# trif_M.net
KiCad netlist of a schematic drawn in EAGLE
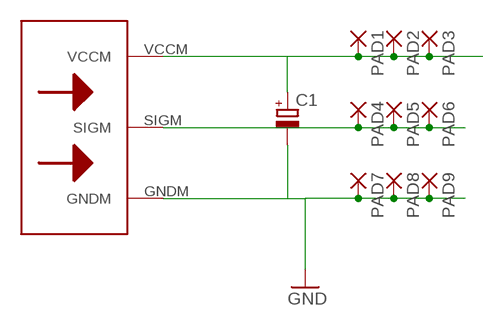
[diagram p0: schematic, sheet 1]

(export (version "E")
  (design (tool "Eeschema 10.0.6"))
  (components
    (comp (ref "C1")
      (value "CPOL-EU153CLV-1012")
      (footprint "eagle-import:153CLV-1012")
      (libsource (lib "eagle-import") (part "CPOL-EU153CLV-1012"))
    )
    (comp (ref "PAD1")
      (value "SMD2")
      (footprint "eagle-import:SMD1,27-2,54")
      (libsource (lib "eagle-import") (part "SMD2"))
    )
    (comp (ref "PAD2")
      (value "SMD2")
      (footprint "eagle-import:SMD1,27-2,54")
      (libsource (lib "eagle-import") (part "SMD2"))
    )
    (comp (ref "PAD3")
      (value "SMD2")
      (footprint "eagle-import:SMD1,27-2,54")
      (libsource (lib "eagle-import") (part "SMD2"))
    )
    (comp (ref "PAD4")
      (value "SMD2")
      (footprint "eagle-import:SMD1,27-2,54")
      (libsource (lib "eagle-import") (part "SMD2"))
    )
    (comp (ref "PAD5")
      (value "SMD2")
      (footprint "eagle-import:SMD1,27-2,54")
      (libsource (lib "eagle-import") (part "SMD2"))
    )
    (comp (ref "PAD6")
      (value "SMD2")
      (footprint "eagle-import:SMD1,27-2,54")
      (libsource (lib "eagle-import") (part "SMD2"))
    )
    (comp (ref "PAD7")
      (value "SMD2")
      (footprint "eagle-import:SMD1,27-2,54")
      (libsource (lib "eagle-import") (part "SMD2"))
    )
    (comp (ref "PAD8")
      (value "SMD2")
      (footprint "eagle-import:SMD1,27-2,54")
      (libsource (lib "eagle-import") (part "SMD2"))
    )
    (comp (ref "PAD9")
      (value "SMD2")
      (footprint "eagle-import:SMD1,27-2,54")
      (libsource (lib "eagle-import") (part "SMD2"))
    )
    (comp (ref "U$1")
      (value "BITWIREM")
      (footprint "eagle-import:BITWIREM")
      (libsource (lib "eagle-import") (part "BITWIREM"))
    )
  )
  (nets
    (net (code "1") (name "GND") (class "Default")
      (node (ref "C1") (pin "-") (pinfunction "-_-") (pintype "passive"))
      (node (ref "PAD7") (pin "1") (pinfunction "P_1") (pintype "passive"))
      (node (ref "PAD8") (pin "1") (pinfunction "P_1") (pintype "passive"))
      (node (ref "PAD9") (pin "1") (pinfunction "P_1") (pintype "passive"))
      (node (ref "U$1") (pin "GNDM") (pinfunction "GNDM_GNDM") (pintype "bidirectional"))
    )
    (net (code "2") (name "Net-(PAD1-P)") (class "Default")
      (node (ref "C1") (pin "+") (pinfunction "+_+") (pintype "passive"))
      (node (ref "PAD1") (pin "1") (pinfunction "P_1") (pintype "passive"))
      (node (ref "PAD2") (pin "1") (pinfunction "P_1") (pintype "passive"))
      (node (ref "PAD3") (pin "1") (pinfunction "P_1") (pintype "passive"))
      (node (ref "U$1") (pin "VCCM") (pinfunction "VCCM_VCCM") (pintype "bidirectional"))
    )
    (net (code "3") (name "Net-(PAD4-P)") (class "Default")
      (node (ref "PAD4") (pin "1") (pinfunction "P_1") (pintype "passive"))
      (node (ref "PAD5") (pin "1") (pinfunction "P_1") (pintype "passive"))
      (node (ref "PAD6") (pin "1") (pinfunction "P_1") (pintype "passive"))
      (node (ref "U$1") (pin "SIGM") (pinfunction "SIGM_SIGM") (pintype "bidirectional"))
    )
  )
)
